# RH047_2.net
KiCad netlist of a schematic drawn in EAGLE
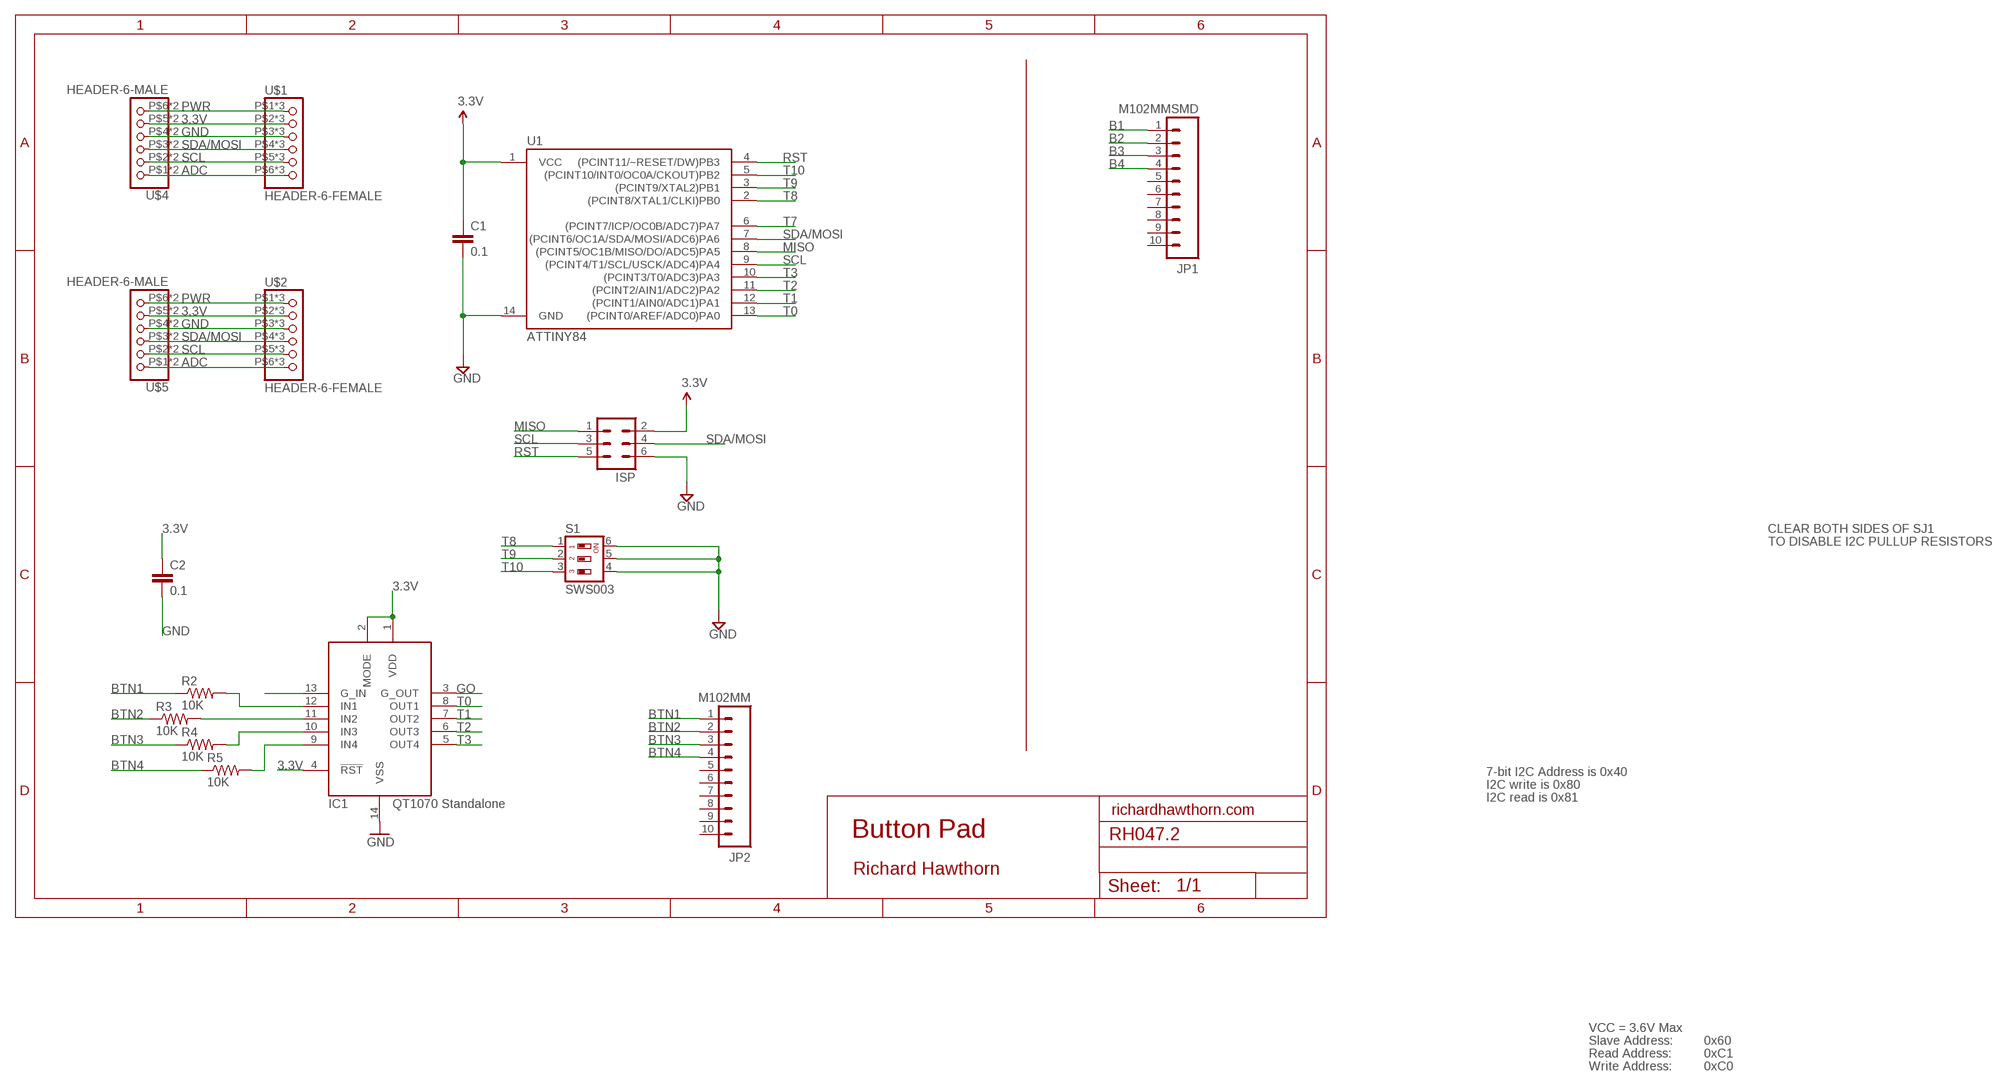
[diagram p0: schematic, sheet 1]

(export (version "E")
  (design (tool "Eeschema 10.0.6"))
  (components
    (comp (ref "C1")
      (value "0.1")
      (footprint "eagle-import:0603-CAP")
      (libsource (lib "eagle-import") (part "CAP0603-CAP"))
    )
    (comp (ref "C2")
      (value "0.1")
      (footprint "eagle-import:0603-CAP")
      (libsource (lib "eagle-import") (part "CAP0603-CAP"))
    )
    (comp (ref "IC1")
      (value "AT42QT1070-SSU")
      (footprint "eagle-import:SO14")
      (libsource (lib "eagle-import") (part "AT42QT1070-SSU"))
    )
    (comp (ref "ISP")
      (value "MA03-2")
      (footprint "eagle-import:MA03-2")
      (libsource (lib "eagle-import") (part "MA03-2"))
    )
    (comp (ref "JP1")
      (value "M102MMSMD")
      (footprint "eagle-import:1X10-2MM-SMD")
      (libsource (lib "eagle-import") (part "M102MMSMD"))
    )
    (comp (ref "JP2")
      (value "M102MM")
      (footprint "eagle-import:1X10-2MM")
      (libsource (lib "eagle-import") (part "M102MM"))
    )
    (comp (ref "R2")
      (value "10K")
      (footprint "eagle-import:R0805")
      (libsource (lib "eagle-import") (part "R-US_R0805"))
    )
    (comp (ref "R3")
      (value "10K")
      (footprint "eagle-import:R0805")
      (libsource (lib "eagle-import") (part "R-US_R0805"))
    )
    (comp (ref "R4")
      (value "10K")
      (footprint "eagle-import:R0805")
      (libsource (lib "eagle-import") (part "R-US_R0805"))
    )
    (comp (ref "R5")
      (value "10K")
      (footprint "eagle-import:R0805")
      (libsource (lib "eagle-import") (part "R-US_R0805"))
    )
    (comp (ref "S1")
      (value "SWS003")
      (footprint "eagle-import:SMS-003")
      (libsource (lib "eagle-import") (part "SWS003"))
    )
    (comp (ref "U$1")
      (value "HEADER-6-FEMALE")
      (footprint "eagle-import:2MMHEADER6")
      (libsource (lib "eagle-import") (part "HEADER-6-FEMALE"))
    )
    (comp (ref "U$2")
      (value "HEADER-6-FEMALE")
      (footprint "eagle-import:2MMHEADER6")
      (libsource (lib "eagle-import") (part "HEADER-6-FEMALE"))
    )
    (comp (ref "U$4")
      (value "HEADER-6-MALE")
      (footprint "eagle-import:2MMHEADERPIN6")
      (libsource (lib "eagle-import") (part "HEADER-6-MALE"))
    )
    (comp (ref "U$5")
      (value "HEADER-6-MALE")
      (footprint "eagle-import:2MMHEADERPIN6")
      (libsource (lib "eagle-import") (part "HEADER-6-MALE"))
    )
    (comp (ref "U1")
      (value "ATTINY84")
      (footprint "eagle-import:SO14")
      (libsource (lib "eagle-import") (part "ATTINY84"))
    )
  )
  (nets
    (net (code "1") (name "/ADC") (class "Default")
      (node (ref "U$1") (pin "P$14") (pinfunction "6_P$14") (pintype "passive"))
      (node (ref "U$1") (pin "P$22") (pinfunction "6_P$22") (pintype "passive"))
      (node (ref "U$1") (pin "P$6") (pinfunction "6_P$6") (pintype "passive"))
      (node (ref "U$2") (pin "P$14") (pinfunction "6_P$14") (pintype "passive"))
      (node (ref "U$2") (pin "P$22") (pinfunction "6_P$22") (pintype "passive"))
      (node (ref "U$2") (pin "P$6") (pinfunction "6_P$6") (pintype "passive"))
      (node (ref "U$4") (pin "P$1") (pinfunction "1_P$1") (pintype "passive"))
      (node (ref "U$4") (pin "P$9") (pinfunction "1_P$9") (pintype "passive"))
      (node (ref "U$5") (pin "P$1") (pinfunction "1_P$1") (pintype "passive"))
      (node (ref "U$5") (pin "P$9") (pinfunction "1_P$9") (pintype "passive"))
    )
    (net (code "2") (name "/B1") (class "Default")
      (node (ref "JP1") (pin "1") (pinfunction "1_1") (pintype "passive"))
    )
    (net (code "3") (name "/B2") (class "Default")
      (node (ref "JP1") (pin "2") (pinfunction "2_2") (pintype "passive"))
    )
    (net (code "4") (name "/B3") (class "Default")
      (node (ref "JP1") (pin "3") (pinfunction "3_3") (pintype "passive"))
    )
    (net (code "5") (name "/B4") (class "Default")
      (node (ref "JP1") (pin "4") (pinfunction "4_4") (pintype "passive"))
    )
    (net (code "6") (name "/BTN1") (class "Default")
      (node (ref "JP2") (pin "1") (pinfunction "1_1") (pintype "passive"))
      (node (ref "R2") (pin "1") (pinfunction "1_1") (pintype "passive"))
    )
    (net (code "7") (name "/BTN2") (class "Default")
      (node (ref "JP2") (pin "2") (pinfunction "2_2") (pintype "passive"))
      (node (ref "R3") (pin "1") (pinfunction "1_1") (pintype "passive"))
    )
    (net (code "8") (name "/BTN3") (class "Default")
      (node (ref "JP2") (pin "3") (pinfunction "3_3") (pintype "passive"))
      (node (ref "R4") (pin "1") (pinfunction "1_1") (pintype "passive"))
    )
    (net (code "9") (name "/BTN4") (class "Default")
      (node (ref "JP2") (pin "4") (pinfunction "4_4") (pintype "passive"))
      (node (ref "R5") (pin "1") (pinfunction "1_1") (pintype "passive"))
    )
    (net (code "10") (name "/GO") (class "Default")
      (node (ref "IC1") (pin "3") (pinfunction "G_OUT_3") (pintype "open_collector"))
    )
    (net (code "11") (name "/MISO") (class "Default")
      (node (ref "ISP") (pin "1") (pinfunction "1_1") (pintype "passive"))
      (node (ref "U1") (pin "8") (pinfunction "(PCINT5/OC1B/MISO/DO/ADC5)PA5_8") (pintype "bidirectional"))
    )
    (net (code "12") (name "/PWR") (class "Default")
      (node (ref "U$1") (pin "P$1") (pinfunction "1_P$1") (pintype "passive"))
      (node (ref "U$1") (pin "P$17") (pinfunction "1_P$17") (pintype "passive"))
      (node (ref "U$1") (pin "P$9") (pinfunction "1_P$9") (pintype "passive"))
      (node (ref "U$2") (pin "P$1") (pinfunction "1_P$1") (pintype "passive"))
      (node (ref "U$2") (pin "P$17") (pinfunction "1_P$17") (pintype "passive"))
      (node (ref "U$2") (pin "P$9") (pinfunction "1_P$9") (pintype "passive"))
      (node (ref "U$4") (pin "P$14") (pinfunction "6_P$14") (pintype "passive"))
      (node (ref "U$4") (pin "P$6") (pinfunction "6_P$6") (pintype "passive"))
      (node (ref "U$5") (pin "P$14") (pinfunction "6_P$14") (pintype "passive"))
      (node (ref "U$5") (pin "P$6") (pinfunction "6_P$6") (pintype "passive"))
    )
    (net (code "13") (name "/RST") (class "Default")
      (node (ref "ISP") (pin "5") (pinfunction "5_5") (pintype "passive"))
      (node (ref "U1") (pin "4") (pinfunction "(PCINT11/~{RESET/DW})PB3_4") (pintype "bidirectional"))
    )
    (net (code "14") (name "/SCL") (class "Default")
      (node (ref "ISP") (pin "3") (pinfunction "3_3") (pintype "passive"))
      (node (ref "U$1") (pin "P$13") (pinfunction "5_P$13") (pintype "passive"))
      (node (ref "U$1") (pin "P$21") (pinfunction "5_P$21") (pintype "passive"))
      (node (ref "U$1") (pin "P$5") (pinfunction "5_P$5") (pintype "passive"))
      (node (ref "U$2") (pin "P$13") (pinfunction "5_P$13") (pintype "passive"))
      (node (ref "U$2") (pin "P$21") (pinfunction "5_P$21") (pintype "passive"))
      (node (ref "U$2") (pin "P$5") (pinfunction "5_P$5") (pintype "passive"))
      (node (ref "U$4") (pin "P$10") (pinfunction "2_P$10") (pintype "passive"))
      (node (ref "U$4") (pin "P$2") (pinfunction "2_P$2") (pintype "passive"))
      (node (ref "U$5") (pin "P$10") (pinfunction "2_P$10") (pintype "passive"))
      (node (ref "U$5") (pin "P$2") (pinfunction "2_P$2") (pintype "passive"))
      (node (ref "U1") (pin "9") (pinfunction "(PCINT4/T1/SCL/USCK/ADC4)PA4_9") (pintype "bidirectional"))
    )
    (net (code "15") (name "/SDA{slash}MOSI") (class "Default")
      (node (ref "ISP") (pin "4") (pinfunction "4_4") (pintype "passive"))
      (node (ref "U$1") (pin "P$12") (pinfunction "4_P$12") (pintype "passive"))
      (node (ref "U$1") (pin "P$20") (pinfunction "4_P$20") (pintype "passive"))
      (node (ref "U$1") (pin "P$4") (pinfunction "4_P$4") (pintype "passive"))
      (node (ref "U$2") (pin "P$12") (pinfunction "4_P$12") (pintype "passive"))
      (node (ref "U$2") (pin "P$20") (pinfunction "4_P$20") (pintype "passive"))
      (node (ref "U$2") (pin "P$4") (pinfunction "4_P$4") (pintype "passive"))
      (node (ref "U$4") (pin "P$11") (pinfunction "3_P$11") (pintype "passive"))
      (node (ref "U$4") (pin "P$3") (pinfunction "3_P$3") (pintype "passive"))
      (node (ref "U$5") (pin "P$11") (pinfunction "3_P$11") (pintype "passive"))
      (node (ref "U$5") (pin "P$3") (pinfunction "3_P$3") (pintype "passive"))
      (node (ref "U1") (pin "7") (pinfunction "(PCINT6/OC1A/SDA/MOSI/ADC6)PA6_7") (pintype "bidirectional"))
    )
    (net (code "16") (name "/T0") (class "Default")
      (node (ref "IC1") (pin "8") (pinfunction "OUT1_8") (pintype "open_collector"))
      (node (ref "U1") (pin "13") (pinfunction "(PCINT0/AREF/ADC0)PA0_13") (pintype "bidirectional"))
    )
    (net (code "17") (name "/T1") (class "Default")
      (node (ref "IC1") (pin "7") (pinfunction "OUT2_7") (pintype "open_collector"))
      (node (ref "U1") (pin "12") (pinfunction "(PCINT1/AIN0/ADC1)PA1_12") (pintype "bidirectional"))
    )
    (net (code "18") (name "/T2") (class "Default")
      (node (ref "IC1") (pin "6") (pinfunction "OUT3_6") (pintype "open_collector"))
      (node (ref "U1") (pin "11") (pinfunction "(PCINT2/AIN1/ADC2)PA2_11") (pintype "bidirectional"))
    )
    (net (code "19") (name "/T3") (class "Default")
      (node (ref "IC1") (pin "5") (pinfunction "OUT4_5") (pintype "open_collector"))
      (node (ref "U1") (pin "10") (pinfunction "(PCINT3/T0/ADC3)PA3_10") (pintype "bidirectional"))
    )
    (net (code "20") (name "/T7") (class "Default")
      (node (ref "U1") (pin "6") (pinfunction "(PCINT7/ICP/OC0B/ADC7)PA7_6") (pintype "bidirectional"))
    )
    (net (code "21") (name "/T8") (class "Default")
      (node (ref "S1") (pin "1") (pinfunction "1_1") (pintype "passive"))
      (node (ref "U1") (pin "2") (pinfunction "(PCINT8/XTAL1/CLKI)PB0_2") (pintype "bidirectional"))
    )
    (net (code "22") (name "/T9") (class "Default")
      (node (ref "S1") (pin "2") (pinfunction "2_2") (pintype "passive"))
      (node (ref "U1") (pin "3") (pinfunction "(PCINT9/XTAL2)PB1_3") (pintype "bidirectional"))
    )
    (net (code "23") (name "/T10") (class "Default")
      (node (ref "S1") (pin "3") (pinfunction "3_3") (pintype "passive"))
      (node (ref "U1") (pin "5") (pinfunction "(PCINT10/INT0/OC0A/CKOUT)PB2_5") (pintype "bidirectional"))
    )
    (net (code "24") (name "3.3V") (class "Default")
      (node (ref "C1") (pin "1") (pinfunction "1_1") (pintype "passive"))
      (node (ref "C2") (pin "1") (pinfunction "1_1") (pintype "passive"))
      (node (ref "IC1") (pin "1") (pinfunction "VDD_1") (pintype "power_in"))
      (node (ref "IC1") (pin "2") (pinfunction "MODE_2") (pintype "input"))
      (node (ref "IC1") (pin "4") (pinfunction "~{RST}_4") (pintype "input"))
      (node (ref "ISP") (pin "2") (pinfunction "2_2") (pintype "passive"))
      (node (ref "U$1") (pin "P$10") (pinfunction "2_P$10") (pintype "passive"))
      (node (ref "U$1") (pin "P$18") (pinfunction "2_P$18") (pintype "passive"))
      (node (ref "U$1") (pin "P$2") (pinfunction "2_P$2") (pintype "passive"))
      (node (ref "U$2") (pin "P$10") (pinfunction "2_P$10") (pintype "passive"))
      (node (ref "U$2") (pin "P$18") (pinfunction "2_P$18") (pintype "passive"))
      (node (ref "U$2") (pin "P$2") (pinfunction "2_P$2") (pintype "passive"))
      (node (ref "U$4") (pin "P$13") (pinfunction "5_P$13") (pintype "passive"))
      (node (ref "U$4") (pin "P$5") (pinfunction "5_P$5") (pintype "passive"))
      (node (ref "U$5") (pin "P$13") (pinfunction "5_P$13") (pintype "passive"))
      (node (ref "U$5") (pin "P$5") (pinfunction "5_P$5") (pintype "passive"))
      (node (ref "U1") (pin "1") (pinfunction "VCC_1") (pintype "bidirectional"))
    )
    (net (code "25") (name "GND") (class "Default")
      (node (ref "C1") (pin "2") (pinfunction "2_2") (pintype "passive"))
      (node (ref "C2") (pin "2") (pinfunction "2_2") (pintype "passive"))
      (node (ref "IC1") (pin "14") (pinfunction "VSS_14") (pintype "power_in"))
      (node (ref "ISP") (pin "6") (pinfunction "6_6") (pintype "passive"))
      (node (ref "S1") (pin "4") (pinfunction "4_4") (pintype "passive"))
      (node (ref "S1") (pin "5") (pinfunction "5_5") (pintype "passive"))
      (node (ref "S1") (pin "6") (pinfunction "6_6") (pintype "passive"))
      (node (ref "U$1") (pin "P$11") (pinfunction "3_P$11") (pintype "passive"))
      (node (ref "U$1") (pin "P$19") (pinfunction "3_P$19") (pintype "passive"))
      (node (ref "U$1") (pin "P$3") (pinfunction "3_P$3") (pintype "passive"))
      (node (ref "U$2") (pin "P$11") (pinfunction "3_P$11") (pintype "passive"))
      (node (ref "U$2") (pin "P$19") (pinfunction "3_P$19") (pintype "passive"))
      (node (ref "U$2") (pin "P$3") (pinfunction "3_P$3") (pintype "passive"))
      (node (ref "U$4") (pin "P$12") (pinfunction "4_P$12") (pintype "passive"))
      (node (ref "U$4") (pin "P$4") (pinfunction "4_P$4") (pintype "passive"))
      (node (ref "U$5") (pin "P$12") (pinfunction "4_P$12") (pintype "passive"))
      (node (ref "U$5") (pin "P$4") (pinfunction "4_P$4") (pintype "passive"))
      (node (ref "U1") (pin "14") (pinfunction "GND_14") (pintype "bidirectional"))
    )
    (net (code "26") (name "Net-(IC1-IN1)") (class "Default")
      (node (ref "IC1") (pin "12") (pinfunction "IN1_12") (pintype "input"))
      (node (ref "R2") (pin "2") (pinfunction "2_2") (pintype "passive"))
    )
    (net (code "27") (name "Net-(IC1-IN2)") (class "Default")
      (node (ref "IC1") (pin "11") (pinfunction "IN2_11") (pintype "input"))
      (node (ref "R3") (pin "2") (pinfunction "2_2") (pintype "passive"))
    )
    (net (code "28") (name "Net-(IC1-IN3)") (class "Default")
      (node (ref "IC1") (pin "10") (pinfunction "IN3_10") (pintype "input"))
      (node (ref "R4") (pin "2") (pinfunction "2_2") (pintype "passive"))
    )
    (net (code "29") (name "Net-(IC1-IN4)") (class "Default")
      (node (ref "IC1") (pin "9") (pinfunction "IN4_9") (pintype "input"))
      (node (ref "R5") (pin "2") (pinfunction "2_2") (pintype "passive"))
    )
    (net (code "30") (name "unconnected-(IC1-G_IN-Pad13)") (class "Default")
      (node (ref "IC1") (pin "13") (pinfunction "G_IN_13") (pintype "input"))
    )
    (net (code "31") (name "unconnected-(JP1-Pad5)") (class "Default")
      (node (ref "JP1") (pin "5") (pinfunction "5_5") (pintype "passive"))
    )
    (net (code "32") (name "unconnected-(JP1-Pad6)") (class "Default")
      (node (ref "JP1") (pin "6") (pinfunction "6_6") (pintype "passive"))
    )
    (net (code "33") (name "unconnected-(JP1-Pad7)") (class "Default")
      (node (ref "JP1") (pin "7") (pinfunction "7_7") (pintype "passive"))
    )
    (net (code "34") (name "unconnected-(JP1-Pad8)") (class "Default")
      (node (ref "JP1") (pin "8") (pinfunction "8_8") (pintype "passive"))
    )
    (net (code "35") (name "unconnected-(JP1-Pad9)") (class "Default")
      (node (ref "JP1") (pin "9") (pinfunction "9_9") (pintype "passive"))
    )
    (net (code "36") (name "unconnected-(JP1-Pad10)") (class "Default")
      (node (ref "JP1") (pin "10") (pinfunction "10_10") (pintype "passive"))
    )
    (net (code "37") (name "unconnected-(JP2-Pad5)") (class "Default")
      (node (ref "JP2") (pin "5") (pinfunction "5_5") (pintype "passive"))
    )
    (net (code "38") (name "unconnected-(JP2-Pad6)") (class "Default")
      (node (ref "JP2") (pin "6") (pinfunction "6_6") (pintype "passive"))
    )
    (net (code "39") (name "unconnected-(JP2-Pad7)") (class "Default")
      (node (ref "JP2") (pin "7") (pinfunction "7_7") (pintype "passive"))
    )
    (net (code "40") (name "unconnected-(JP2-Pad8)") (class "Default")
      (node (ref "JP2") (pin "8") (pinfunction "8_8") (pintype "passive"))
    )
    (net (code "41") (name "unconnected-(JP2-Pad9)") (class "Default")
      (node (ref "JP2") (pin "9") (pinfunction "9_9") (pintype "passive"))
    )
    (net (code "42") (name "unconnected-(JP2-Pad10)") (class "Default")
      (node (ref "JP2") (pin "10") (pinfunction "10_10") (pintype "passive"))
    )
  )
)
